# Sprite_CC1310_Development.net
KiCad netlist of a schematic drawn in EAGLE
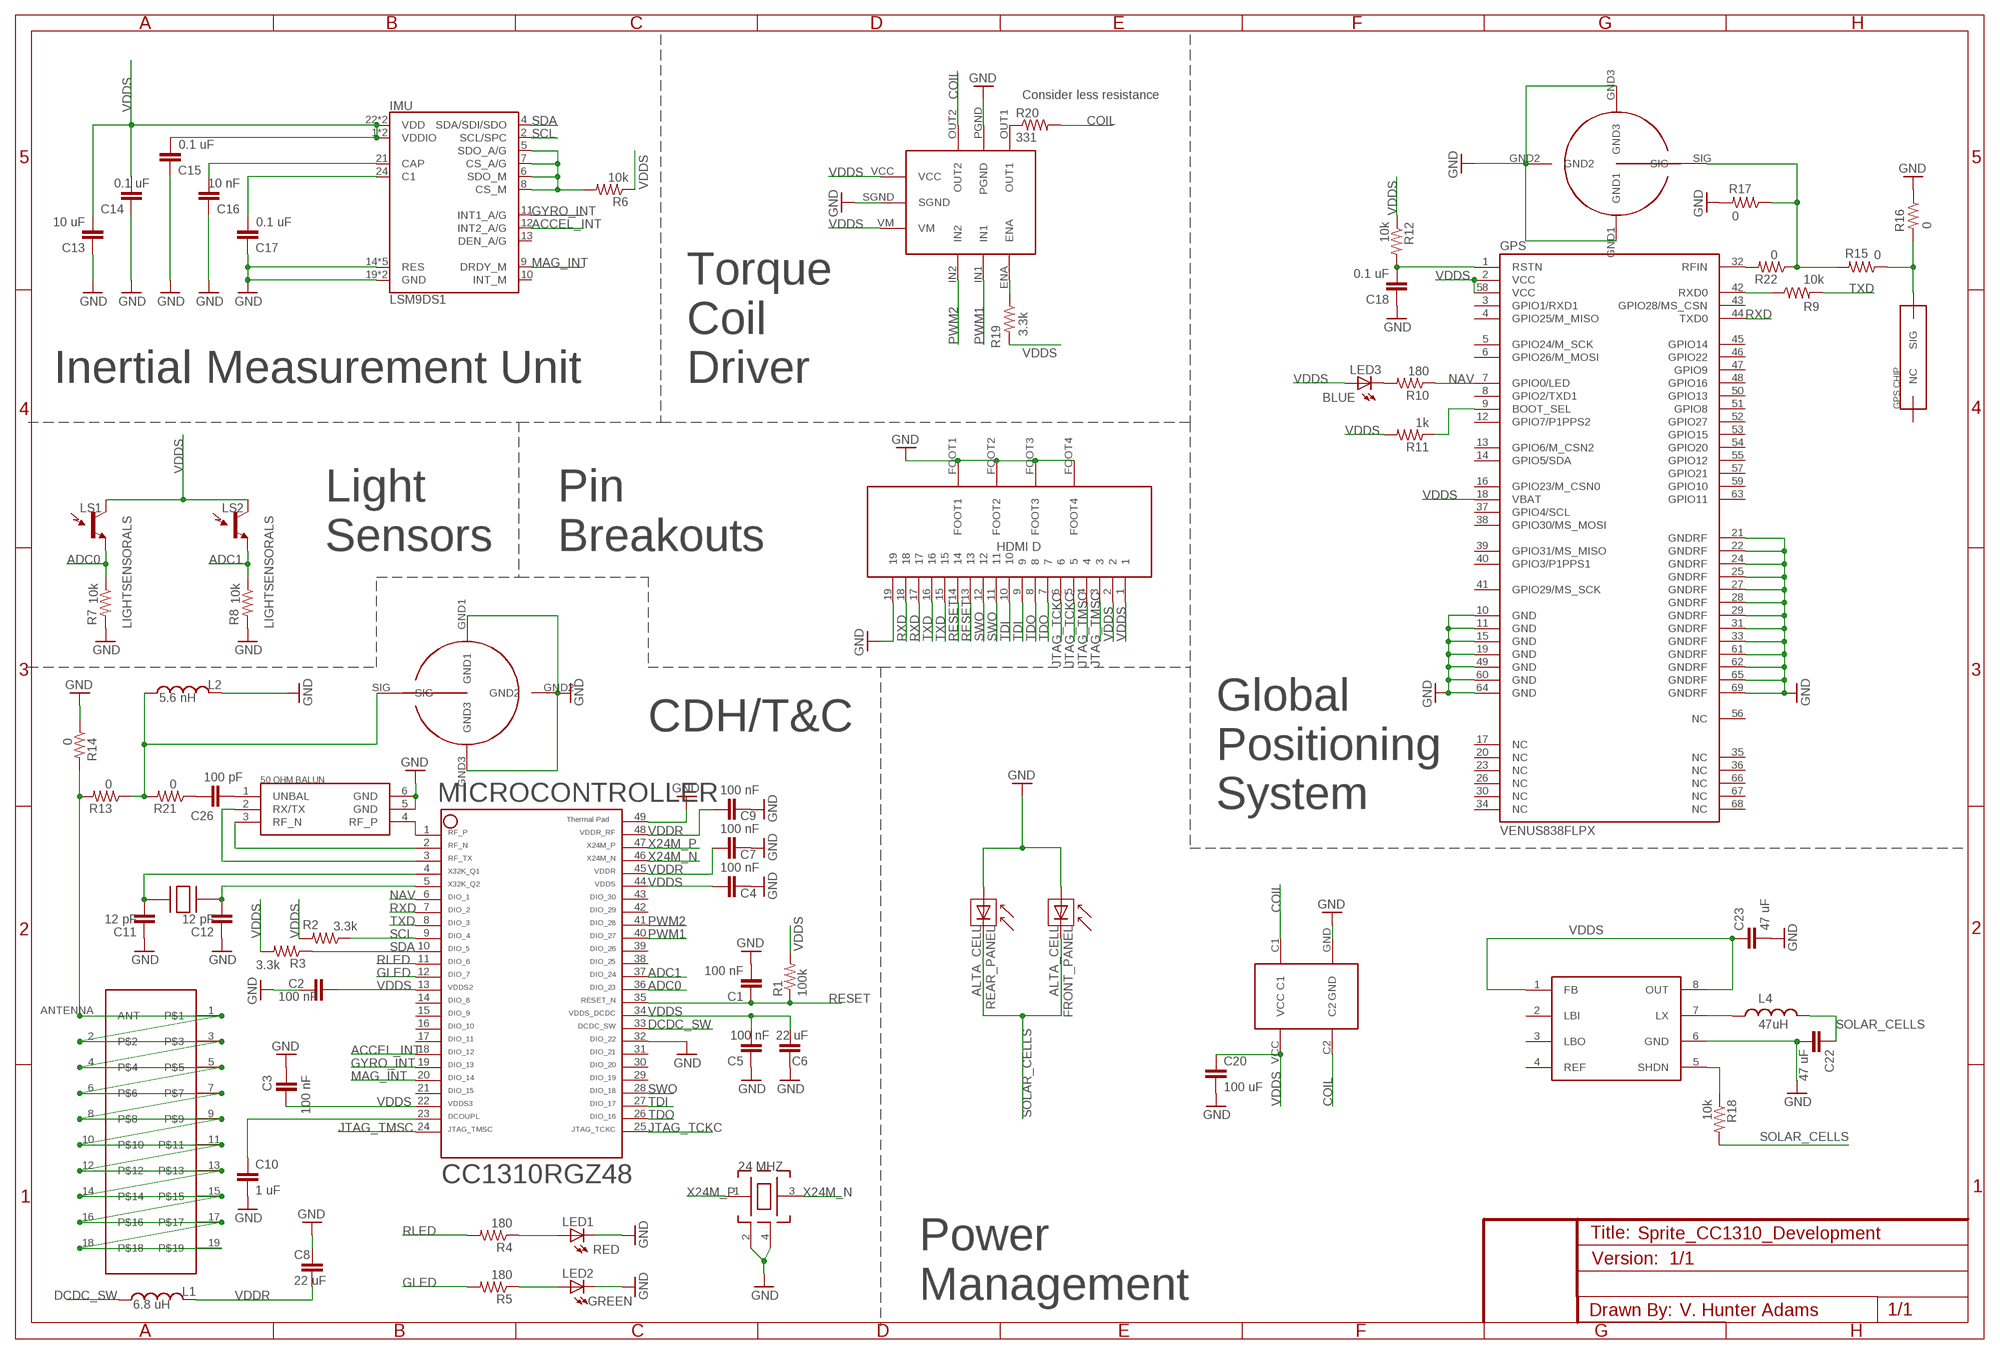
[diagram p0: schematic, sheet 1]

(export (version "E")
  (design (tool "Eeschema 10.0.6"))
  (components
    (comp (ref "32.768")
      (value "FC-135")
      (footprint "eagle-import:FC-135")
      (libsource (lib "eagle-import") (part "FC-135"))
    )
    (comp (ref "BALUN")
      (value "JOHANSON_BALUN")
      (footprint "eagle-import:JOHANSON_BALUN")
      (libsource (lib "eagle-import") (part "JOHANSON_BALUN"))
    )
    (comp (ref "C1")
      (value "100 nF")
      (footprint "eagle-import:0402-CAP")
      (libsource (lib "eagle-import") (part "CAP0402-CAP"))
    )
    (comp (ref "C2")
      (value "100 nF")
      (footprint "eagle-import:0402-CAP")
      (libsource (lib "eagle-import") (part "CAP0402-CAP"))
    )
    (comp (ref "C3")
      (value "100 nF")
      (footprint "eagle-import:0402-CAP")
      (libsource (lib "eagle-import") (part "CAP0402-CAP"))
    )
    (comp (ref "C4")
      (value "100 nF")
      (footprint "eagle-import:0402-CAP")
      (libsource (lib "eagle-import") (part "CAP0402-CAP"))
    )
    (comp (ref "C5")
      (value "100 nF")
      (footprint "eagle-import:0402-CAP")
      (libsource (lib "eagle-import") (part "CAP0402-CAP"))
    )
    (comp (ref "C6")
      (value "22 uF")
      (footprint "eagle-import:0402-CAP")
      (libsource (lib "eagle-import") (part "CAP0402-CAP"))
    )
    (comp (ref "C7")
      (value "100 nF")
      (footprint "eagle-import:0402-CAP")
      (libsource (lib "eagle-import") (part "CAP0402-CAP"))
    )
    (comp (ref "C8")
      (value "22 uF")
      (footprint "eagle-import:0402-CAP")
      (libsource (lib "eagle-import") (part "CAP0402-CAP"))
    )
    (comp (ref "C9")
      (value "100 nF")
      (footprint "eagle-import:0402-CAP")
      (libsource (lib "eagle-import") (part "CAP0402-CAP"))
    )
    (comp (ref "C10")
      (value "1 uF")
      (footprint "eagle-import:0402-CAP")
      (libsource (lib "eagle-import") (part "CAP0402-CAP"))
    )
    (comp (ref "C11")
      (value "12 pF")
      (footprint "eagle-import:0402-CAP")
      (libsource (lib "eagle-import") (part "CAP0402-CAP"))
    )
    (comp (ref "C12")
      (value "12 pF")
      (footprint "eagle-import:0402-CAP")
      (libsource (lib "eagle-import") (part "CAP0402-CAP"))
    )
    (comp (ref "C13")
      (value "10 uF")
      (footprint "eagle-import:0402-CAP")
      (libsource (lib "eagle-import") (part "CAP0402-CAP"))
    )
    (comp (ref "C14")
      (value "0.1 uF")
      (footprint "eagle-import:0402-CAP")
      (libsource (lib "eagle-import") (part "CAP0402-CAP"))
    )
    (comp (ref "C15")
      (value "0.1 uF")
      (footprint "eagle-import:0402-CAP")
      (libsource (lib "eagle-import") (part "CAP0402-CAP"))
    )
    (comp (ref "C16")
      (value "10 nF")
      (footprint "eagle-import:0402-CAP")
      (libsource (lib "eagle-import") (part "CAP0402-CAP"))
    )
    (comp (ref "C17")
      (value "0.1 uF")
      (footprint "eagle-import:0402-CAP")
      (libsource (lib "eagle-import") (part "CAP0402-CAP"))
    )
    (comp (ref "C18")
      (value "0.1 uF")
      (footprint "eagle-import:0402-CAP")
      (libsource (lib "eagle-import") (part "CAP0402-CAP"))
    )
    (comp (ref "C20")
      (value "100 uF")
      (footprint "eagle-import:0805")
      (libsource (lib "eagle-import") (part "CAP0805"))
    )
    (comp (ref "C22")
      (value "47 uF")
      (footprint "eagle-import:0805")
      (libsource (lib "eagle-import") (part "CAP0805"))
    )
    (comp (ref "C23")
      (value "47 uF")
      (footprint "eagle-import:0805")
      (libsource (lib "eagle-import") (part "CAP0805"))
    )
    (comp (ref "C26")
      (value "100 pF")
      (footprint "eagle-import:0402-CAP")
      (libsource (lib "eagle-import") (part "CAP0402-CAP"))
    )
    (comp (ref "FRONT_PANEL")
      (value "ALTA_CELL")
      (footprint "eagle-import:ALTA_CELL")
      (libsource (lib "eagle-import") (part "ALTA_CELL"))
    )
    (comp (ref "GPS")
      (value "VENUS838FLPX")
      (footprint "eagle-import:VENUS838FLPX")
      (libsource (lib "eagle-import") (part "VENUS838FLPX"))
    )
    (comp (ref "IMU")
      (value "LSM9DS1")
      (footprint "eagle-import:LGA24-8X4")
      (libsource (lib "eagle-import") (part "LSM9DS1"))
    )
    (comp (ref "L1")
      (value "6.8 uH")
      (footprint "eagle-import:0603")
      (libsource (lib "eagle-import") (part "INDUCTOR0603"))
    )
    (comp (ref "L2")
      (value "5.6 nH")
      (footprint "eagle-import:0603")
      (libsource (lib "eagle-import") (part "INDUCTOR0603"))
    )
    (comp (ref "L4")
      (value "47uH")
      (footprint "eagle-import:0603")
      (libsource (lib "eagle-import") (part "INDUCTOR0603"))
    )
    (comp (ref "LED1")
      (value "RED")
      (footprint "eagle-import:LED-0603")
      (libsource (lib "eagle-import") (part "LED0603"))
    )
    (comp (ref "LED2")
      (value "GREEN")
      (footprint "eagle-import:LED-0603")
      (libsource (lib "eagle-import") (part "LED0603"))
    )
    (comp (ref "LED3")
      (value "BLUE")
      (footprint "eagle-import:LED-0603")
      (libsource (lib "eagle-import") (part "LED0603"))
    )
    (comp (ref "LS1")
      (value "LIGHTSENSORALS")
      (footprint "eagle-import:ALS-PT19")
      (libsource (lib "eagle-import") (part "LIGHTSENSORALS"))
    )
    (comp (ref "LS2")
      (value "LIGHTSENSORALS")
      (footprint "eagle-import:ALS-PT19")
      (libsource (lib "eagle-import") (part "LIGHTSENSORALS"))
    )
    (comp (ref "MICROCONTROLLER")
      (value "CC1310")
      (footprint "eagle-import:CC1310")
      (libsource (lib "eagle-import") (part "CC1310"))
    )
    (comp (ref "R1")
      (value "100k")
      (footprint "eagle-import:0402-RES")
      (libsource (lib "eagle-import") (part "RESISTOR0402-RES"))
    )
    (comp (ref "R2")
      (value "3.3k")
      (footprint "eagle-import:0402-RES")
      (libsource (lib "eagle-import") (part "RESISTOR0402-RES"))
    )
    (comp (ref "R3")
      (value "3.3k")
      (footprint "eagle-import:0402-RES")
      (libsource (lib "eagle-import") (part "RESISTOR0402-RES"))
    )
    (comp (ref "R4")
      (value "180")
      (footprint "eagle-import:0402-RES")
      (libsource (lib "eagle-import") (part "RESISTOR0402-RES"))
    )
    (comp (ref "R5")
      (value "180")
      (footprint "eagle-import:0402-RES")
      (libsource (lib "eagle-import") (part "RESISTOR0402-RES"))
    )
    (comp (ref "R6")
      (value "10k")
      (footprint "eagle-import:0402-RES")
      (libsource (lib "eagle-import") (part "RESISTOR0402-RES"))
    )
    (comp (ref "R7")
      (value "10k")
      (footprint "eagle-import:0402-RES")
      (libsource (lib "eagle-import") (part "RESISTOR0402-RES"))
    )
    (comp (ref "R8")
      (value "10k")
      (footprint "eagle-import:0402-RES")
      (libsource (lib "eagle-import") (part "RESISTOR0402-RES"))
    )
    (comp (ref "R9")
      (value "10k")
      (footprint "eagle-import:0402-RES")
      (libsource (lib "eagle-import") (part "RESISTOR0402-RES"))
    )
    (comp (ref "R10")
      (value "180")
      (footprint "eagle-import:0402-RES")
      (libsource (lib "eagle-import") (part "RESISTOR0402-RES"))
    )
    (comp (ref "R11")
      (value "1k")
      (footprint "eagle-import:0402-RES")
      (libsource (lib "eagle-import") (part "RESISTOR0402-RES"))
    )
    (comp (ref "R12")
      (value "10k")
      (footprint "eagle-import:0402-RES")
      (libsource (lib "eagle-import") (part "RESISTOR0402-RES"))
    )
    (comp (ref "R13")
      (value "0")
      (footprint "eagle-import:0603-RES")
      (libsource (lib "eagle-import") (part "RESISTOR0603-RES"))
    )
    (comp (ref "R14")
      (value "0")
      (footprint "eagle-import:0603-RES")
      (libsource (lib "eagle-import") (part "RESISTOR0603-RES"))
    )
    (comp (ref "R15")
      (value "0")
      (footprint "eagle-import:0603-RES")
      (libsource (lib "eagle-import") (part "RESISTOR0603-RES"))
    )
    (comp (ref "R16")
      (value "0")
      (footprint "eagle-import:0603-RES")
      (libsource (lib "eagle-import") (part "RESISTOR0603-RES"))
    )
    (comp (ref "R17")
      (value "0")
      (footprint "eagle-import:0603-RES")
      (libsource (lib "eagle-import") (part "RESISTOR0603-RES"))
    )
    (comp (ref "R18")
      (value "10k")
      (footprint "eagle-import:0402-RES")
      (libsource (lib "eagle-import") (part "RESISTOR0402-RES"))
    )
    (comp (ref "R19")
      (value "3.3k")
      (footprint "eagle-import:0402-RES")
      (libsource (lib "eagle-import") (part "RESISTOR0402-RES"))
    )
    (comp (ref "R20")
      (value "331")
      (footprint "eagle-import:0402-RES")
      (libsource (lib "eagle-import") (part "RESISTOR0402-RES"))
    )
    (comp (ref "R21")
      (value "0")
      (footprint "eagle-import:0603-RES")
      (libsource (lib "eagle-import") (part "RESISTOR0603-RES"))
    )
    (comp (ref "R22")
      (value "0")
      (footprint "eagle-import:0603-RES")
      (libsource (lib "eagle-import") (part "RESISTOR0603-RES"))
    )
    (comp (ref "REAR_PANEL")
      (value "ALTA_CELL")
      (footprint "eagle-import:ALTA_CELL")
      (libsource (lib "eagle-import") (part "ALTA_CELL"))
    )
    (comp (ref "TSX3225")
      (value "TSX-3225")
      (footprint "eagle-import:TSX-3225")
      (libsource (lib "eagle-import") (part "TSX-3225"))
    )
    (comp (ref "U$1")
      (value "HDMID")
      (footprint "eagle-import:HDMID")
      (libsource (lib "eagle-import") (part "HDMID"))
    )
    (comp (ref "U$2")
      (value "LV8417CS")
      (footprint "eagle-import:LV8417CS")
      (libsource (lib "eagle-import") (part "LV8417CS"))
    )
    (comp (ref "U$3")
      (value "MM5329-2700")
      (footprint "eagle-import:MM5829-2700")
      (libsource (lib "eagle-import") (part "MM5329-2700"))
    )
    (comp (ref "U$4")
      (value "PANASONIC_RECTIFIER")
      (footprint "eagle-import:PANASONIC_RECTIFIER")
      (libsource (lib "eagle-import") (part "PANASONIC_RECTIFIER"))
    )
    (comp (ref "U$5")
      (value "JOHANSON_GPS_CHIP")
      (footprint "eagle-import:JOHANSON_GPS_CHIP")
      (libsource (lib "eagle-import") (part "JOHANSON_GPS_CHIP"))
    )
    (comp (ref "U$6")
      (value "PCB_ANTENNA")
      (footprint "eagle-import:PCB_ANTENNA")
      (libsource (lib "eagle-import") (part "PCB_ANTENNA"))
    )
    (comp (ref "U$7")
      (value "MM5329-2700")
      (footprint "eagle-import:MM5829-2700")
      (libsource (lib "eagle-import") (part "MM5329-2700"))
    )
    (comp (ref "U$8")
      (value "L6920")
      (footprint "eagle-import:L6920")
      (libsource (lib "eagle-import") (part "L6920"))
    )
  )
  (nets
    (net (code "1") (name "/ACCEL_INT") (class "Default")
      (node (ref "IMU") (pin "12") (pinfunction "INT2_A/G_12") (pintype "bidirectional"))
      (node (ref "MICROCONTROLLER") (pin "18") (pinfunction "18_18") (pintype "bidirectional"))
    )
    (net (code "2") (name "/ADC0") (class "Default")
      (node (ref "LS1") (pin "E") (pinfunction "E1_E") (pintype "passive"))
      (node (ref "MICROCONTROLLER") (pin "36") (pinfunction "36_36") (pintype "bidirectional"))
      (node (ref "R7") (pin "1") (pinfunction "1_1") (pintype "passive"))
    )
    (net (code "3") (name "/ADC1") (class "Default")
      (node (ref "LS2") (pin "E") (pinfunction "E1_E") (pintype "passive"))
      (node (ref "MICROCONTROLLER") (pin "37") (pinfunction "37_37") (pintype "bidirectional"))
      (node (ref "R8") (pin "1") (pinfunction "1_1") (pintype "passive"))
    )
    (net (code "4") (name "/COIL") (class "Default")
      (node (ref "R20") (pin "2") (pinfunction "2_2") (pintype "passive"))
      (node (ref "U$2") (pin "OUT2") (pinfunction "OUT2_OUT2") (pintype "bidirectional"))
      (node (ref "U$4") (pin "C1") (pinfunction "C1_C1") (pintype "bidirectional"))
      (node (ref "U$4") (pin "C2") (pinfunction "C2_C2") (pintype "bidirectional"))
    )
    (net (code "5") (name "/DCDC_SW") (class "Default")
      (node (ref "L1") (pin "1") (pinfunction "1_1") (pintype "passive"))
      (node (ref "MICROCONTROLLER") (pin "33") (pinfunction "33_33") (pintype "power_in"))
    )
    (net (code "6") (name "/GLED") (class "Default")
      (node (ref "MICROCONTROLLER") (pin "12") (pinfunction "12_12") (pintype "bidirectional"))
      (node (ref "R5") (pin "2") (pinfunction "2_2") (pintype "passive"))
    )
    (net (code "7") (name "/GYRO_INT") (class "Default")
      (node (ref "IMU") (pin "11") (pinfunction "INT1_A/G_11") (pintype "bidirectional"))
      (node (ref "MICROCONTROLLER") (pin "19") (pinfunction "19_19") (pintype "bidirectional"))
    )
    (net (code "8") (name "/JTAG_TCKC") (class "Default")
      (node (ref "MICROCONTROLLER") (pin "25") (pinfunction "25_25") (pintype "input"))
      (node (ref "U$1") (pin "5") (pinfunction "5_5") (pintype "bidirectional"))
      (node (ref "U$1") (pin "6") (pinfunction "6_6") (pintype "bidirectional"))
    )
    (net (code "9") (name "/JTAG_TMSC") (class "Default")
      (node (ref "MICROCONTROLLER") (pin "24") (pinfunction "24_24") (pintype "bidirectional"))
      (node (ref "U$1") (pin "3") (pinfunction "3_3") (pintype "bidirectional"))
      (node (ref "U$1") (pin "4") (pinfunction "4_4") (pintype "bidirectional"))
    )
    (net (code "10") (name "/MAG_INT") (class "Default")
      (node (ref "IMU") (pin "9") (pinfunction "DRDY_M_9") (pintype "bidirectional"))
      (node (ref "MICROCONTROLLER") (pin "20") (pinfunction "20_20") (pintype "bidirectional"))
    )
    (net (code "11") (name "/NAV") (class "Default")
      (node (ref "GPS") (pin "7") (pinfunction "GPIO0/LED_7") (pintype "bidirectional"))
      (node (ref "MICROCONTROLLER") (pin "6") (pinfunction "6_6") (pintype "bidirectional"))
      (node (ref "R10") (pin "1") (pinfunction "1_1") (pintype "passive"))
    )
    (net (code "12") (name "/PWM1") (class "Default")
      (node (ref "MICROCONTROLLER") (pin "40") (pinfunction "40_40") (pintype "bidirectional"))
      (node (ref "U$2") (pin "IN1") (pinfunction "IN1_IN1") (pintype "bidirectional"))
    )
    (net (code "13") (name "/PWM2") (class "Default")
      (node (ref "MICROCONTROLLER") (pin "41") (pinfunction "41_41") (pintype "bidirectional"))
      (node (ref "U$2") (pin "IN2") (pinfunction "IN2_IN2") (pintype "bidirectional"))
    )
    (net (code "14") (name "/RESET") (class "Default")
      (node (ref "C1") (pin "1") (pinfunction "1_1") (pintype "passive"))
      (node (ref "MICROCONTROLLER") (pin "35") (pinfunction "35_35") (pintype "input"))
      (node (ref "R1") (pin "1") (pinfunction "1_1") (pintype "passive"))
      (node (ref "U$1") (pin "13") (pinfunction "13_13") (pintype "bidirectional"))
      (node (ref "U$1") (pin "14") (pinfunction "14_14") (pintype "bidirectional"))
    )
    (net (code "15") (name "/RLED") (class "Default")
      (node (ref "MICROCONTROLLER") (pin "11") (pinfunction "11_11") (pintype "bidirectional"))
      (node (ref "R4") (pin "2") (pinfunction "2_2") (pintype "passive"))
    )
    (net (code "16") (name "/RXD") (class "Default")
      (node (ref "GPS") (pin "44") (pinfunction "TXD0_44") (pintype "bidirectional"))
      (node (ref "MICROCONTROLLER") (pin "7") (pinfunction "7_7") (pintype "bidirectional"))
      (node (ref "U$1") (pin "17") (pinfunction "17_17") (pintype "bidirectional"))
      (node (ref "U$1") (pin "18") (pinfunction "18_18") (pintype "bidirectional"))
    )
    (net (code "17") (name "/SCL") (class "Default")
      (node (ref "IMU") (pin "2") (pinfunction "SCL/SPC_2") (pintype "bidirectional"))
      (node (ref "MICROCONTROLLER") (pin "9") (pinfunction "9_9") (pintype "bidirectional"))
      (node (ref "R2") (pin "1") (pinfunction "1_1") (pintype "passive"))
    )
    (net (code "18") (name "/SDA") (class "Default")
      (node (ref "IMU") (pin "4") (pinfunction "SDA/SDI/SDO_4") (pintype "bidirectional"))
      (node (ref "MICROCONTROLLER") (pin "10") (pinfunction "10_10") (pintype "bidirectional"))
      (node (ref "R3") (pin "1") (pinfunction "1_1") (pintype "passive"))
    )
    (net (code "19") (name "/SOLAR_CELLS") (class "Default")
      (node (ref "C22") (pin "1") (pinfunction "1_1") (pintype "passive"))
      (node (ref "FRONT_PANEL") (pin "+") (pinfunction "+_+") (pintype "passive"))
      (node (ref "L4") (pin "2") (pinfunction "2_2") (pintype "passive"))
      (node (ref "R18") (pin "2") (pinfunction "2_2") (pintype "passive"))
      (node (ref "REAR_PANEL") (pin "+") (pinfunction "+_+") (pintype "passive"))
    )
    (net (code "20") (name "/SWO") (class "Default")
      (node (ref "MICROCONTROLLER") (pin "28") (pinfunction "28_28") (pintype "bidirectional"))
      (node (ref "U$1") (pin "11") (pinfunction "11_11") (pintype "bidirectional"))
      (node (ref "U$1") (pin "12") (pinfunction "12_12") (pintype "bidirectional"))
    )
    (net (code "21") (name "/TDI") (class "Default")
      (node (ref "MICROCONTROLLER") (pin "27") (pinfunction "27_27") (pintype "bidirectional"))
      (node (ref "U$1") (pin "10") (pinfunction "10_10") (pintype "bidirectional"))
      (node (ref "U$1") (pin "9") (pinfunction "9_9") (pintype "bidirectional"))
    )
    (net (code "22") (name "/TDO") (class "Default")
      (node (ref "MICROCONTROLLER") (pin "26") (pinfunction "26_26") (pintype "bidirectional"))
      (node (ref "U$1") (pin "7") (pinfunction "7_7") (pintype "bidirectional"))
      (node (ref "U$1") (pin "8") (pinfunction "8_8") (pintype "bidirectional"))
    )
    (net (code "23") (name "/TXD") (class "Default")
      (node (ref "MICROCONTROLLER") (pin "8") (pinfunction "8_8") (pintype "bidirectional"))
      (node (ref "R9") (pin "2") (pinfunction "2_2") (pintype "passive"))
      (node (ref "U$1") (pin "15") (pinfunction "15_15") (pintype "bidirectional"))
      (node (ref "U$1") (pin "16") (pinfunction "16_16") (pintype "bidirectional"))
    )
    (net (code "24") (name "/VDDR") (class "Default")
      (node (ref "C7") (pin "1") (pinfunction "1_1") (pintype "passive"))
      (node (ref "C8") (pin "1") (pinfunction "1_1") (pintype "passive"))
      (node (ref "C9") (pin "1") (pinfunction "1_1") (pintype "passive"))
      (node (ref "L1") (pin "2") (pinfunction "2_2") (pintype "passive"))
      (node (ref "MICROCONTROLLER") (pin "45") (pinfunction "45_45") (pintype "power_in"))
      (node (ref "MICROCONTROLLER") (pin "48") (pinfunction "48_48") (pintype "power_in"))
    )
    (net (code "25") (name "/VDDS") (class "Default")
      (node (ref "C13") (pin "1") (pinfunction "1_1") (pintype "passive"))
      (node (ref "C14") (pin "1") (pinfunction "1_1") (pintype "passive"))
      (node (ref "C15") (pin "1") (pinfunction "1_1") (pintype "passive"))
      (node (ref "C2") (pin "1") (pinfunction "1_1") (pintype "passive"))
      (node (ref "C20") (pin "1") (pinfunction "1_1") (pintype "passive"))
      (node (ref "C23") (pin "1") (pinfunction "1_1") (pintype "passive"))
      (node (ref "C3") (pin "1") (pinfunction "1_1") (pintype "passive"))
      (node (ref "C4") (pin "1") (pinfunction "1_1") (pintype "passive"))
      (node (ref "C5") (pin "1") (pinfunction "1_1") (pintype "passive"))
      (node (ref "C6") (pin "1") (pinfunction "1_1") (pintype "passive"))
      (node (ref "GPS") (pin "18") (pinfunction "VBAT_18") (pintype "bidirectional"))
      (node (ref "GPS") (pin "2") (pinfunction "VCC_2") (pintype "bidirectional"))
      (node (ref "GPS") (pin "58") (pinfunction "VCC_58") (pintype "bidirectional"))
      (node (ref "IMU") (pin "1") (pinfunction "VDDIO_1") (pintype "bidirectional"))
      (node (ref "IMU") (pin "22") (pinfunction "VDD_22") (pintype "bidirectional"))
      (node (ref "IMU") (pin "23") (pinfunction "VDD_23") (pintype "bidirectional"))
      (node (ref "IMU") (pin "3") (pinfunction "VDDIO_3") (pintype "bidirectional"))
      (node (ref "LED3") (pin "A") (pinfunction "A_A") (pintype "passive"))
      (node (ref "LS1") (pin "C") (pinfunction "C1_C") (pintype "passive"))
      (node (ref "LS2") (pin "C") (pinfunction "C1_C") (pintype "passive"))
      (node (ref "MICROCONTROLLER") (pin "13") (pinfunction "13_13") (pintype "bidirectional"))
      (node (ref "MICROCONTROLLER") (pin "22") (pinfunction "22_22") (pintype "power_in"))
      (node (ref "MICROCONTROLLER") (pin "34") (pinfunction "34_34") (pintype "power_in"))
      (node (ref "MICROCONTROLLER") (pin "44") (pinfunction "44_44") (pintype "power_in"))
      (node (ref "R1") (pin "2") (pinfunction "2_2") (pintype "passive"))
      (node (ref "R11") (pin "2") (pinfunction "2_2") (pintype "passive"))
      (node (ref "R12") (pin "1") (pinfunction "1_1") (pintype "passive"))
      (node (ref "R19") (pin "2") (pinfunction "2_2") (pintype "passive"))
      (node (ref "R2") (pin "2") (pinfunction "2_2") (pintype "passive"))
      (node (ref "R3") (pin "2") (pinfunction "2_2") (pintype "passive"))
      (node (ref "R6") (pin "1") (pinfunction "1_1") (pintype "passive"))
      (node (ref "U$1") (pin "1") (pinfunction "1_1") (pintype "bidirectional"))
      (node (ref "U$1") (pin "2") (pinfunction "2_2") (pintype "bidirectional"))
      (node (ref "U$2") (pin "VCC") (pinfunction "VCC_VCC") (pintype "bidirectional"))
      (node (ref "U$2") (pin "VM") (pinfunction "VM_VM") (pintype "bidirectional"))
      (node (ref "U$4") (pin "VCC") (pinfunction "VCC_VCC") (pintype "bidirectional"))
      (node (ref "U$8") (pin "1") (pinfunction "FB_1") (pintype "bidirectional"))
      (node (ref "U$8") (pin "8") (pinfunction "OUT_8") (pintype "bidirectional"))
    )
    (net (code "26") (name "/X24M_N") (class "Default")
      (node (ref "MICROCONTROLLER") (pin "46") (pinfunction "46_46") (pintype "bidirectional"))
      (node (ref "TSX3225") (pin "3") (pinfunction "3_3") (pintype "bidirectional"))
    )
    (net (code "27") (name "/X24M_P") (class "Default")
      (node (ref "MICROCONTROLLER") (pin "47") (pinfunction "47_47") (pintype "input"))
      (node (ref "TSX3225") (pin "1") (pinfunction "1_1") (pintype "bidirectional"))
    )
    (net (code "28") (name "GND") (class "Default")
      (node (ref "BALUN") (pin "5") (pinfunction "GND_5") (pintype "bidirectional"))
      (node (ref "BALUN") (pin "6") (pinfunction "GND_6") (pintype "bidirectional"))
      (node (ref "C1") (pin "2") (pinfunction "2_2") (pintype "passive"))
      (node (ref "C10") (pin "2") (pinfunction "2_2") (pintype "passive"))
      (node (ref "C11") (pin "2") (pinfunction "2_2") (pintype "passive"))
      (node (ref "C12") (pin "2") (pinfunction "2_2") (pintype "passive"))
      (node (ref "C13") (pin "2") (pinfunction "2_2") (pintype "passive"))
      (node (ref "C14") (pin "2") (pinfunction "2_2") (pintype "passive"))
      (node (ref "C15") (pin "2") (pinfunction "2_2") (pintype "passive"))
      (node (ref "C16") (pin "2") (pinfunction "2_2") (pintype "passive"))
      (node (ref "C17") (pin "2") (pinfunction "2_2") (pintype "passive"))
      (node (ref "C18") (pin "2") (pinfunction "2_2") (pintype "passive"))
      (node (ref "C2") (pin "2") (pinfunction "2_2") (pintype "passive"))
      (node (ref "C20") (pin "2") (pinfunction "2_2") (pintype "passive"))
      (node (ref "C22") (pin "2") (pinfunction "2_2") (pintype "passive"))
      (node (ref "C23") (pin "2") (pinfunction "2_2") (pintype "passive"))
      (node (ref "C3") (pin "2") (pinfunction "2_2") (pintype "passive"))
      (node (ref "C4") (pin "2") (pinfunction "2_2") (pintype "passive"))
      (node (ref "C5") (pin "2") (pinfunction "2_2") (pintype "passive"))
      (node (ref "C6") (pin "2") (pinfunction "2_2") (pintype "passive"))
      (node (ref "C7") (pin "2") (pinfunction "2_2") (pintype "passive"))
      (node (ref "C8") (pin "2") (pinfunction "2_2") (pintype "passive"))
      (node (ref "C9") (pin "2") (pinfunction "2_2") (pintype "passive"))
      (node (ref "FRONT_PANEL") (pin "-") (pinfunction "-_-") (pintype "passive"))
      (node (ref "GPS") (pin "10") (pinfunction "GND_10") (pintype "bidirectional"))
      (node (ref "GPS") (pin "11") (pinfunction "GND_11") (pintype "bidirectional"))
      (node (ref "GPS") (pin "15") (pinfunction "GND_15") (pintype "bidirectional"))
      (node (ref "GPS") (pin "19") (pinfunction "GND_19") (pintype "bidirectional"))
      (node (ref "GPS") (pin "21") (pinfunction "GNDRF_21") (pintype "bidirectional"))
      (node (ref "GPS") (pin "22") (pinfunction "GNDRF_22") (pintype "bidirectional"))
      (node (ref "GPS") (pin "24") (pinfunction "GNDRF_24") (pintype "bidirectional"))
      (node (ref "GPS") (pin "25") (pinfunction "GNDRF_25") (pintype "bidirectional"))
      (node (ref "GPS") (pin "27") (pinfunction "GNDRF_27") (pintype "bidirectional"))
      (node (ref "GPS") (pin "28") (pinfunction "GNDRF_28") (pintype "bidirectional"))
      (node (ref "GPS") (pin "29") (pinfunction "GNDRF_29") (pintype "bidirectional"))
      (node (ref "GPS") (pin "31") (pinfunction "GNDRF_31") (pintype "bidirectional"))
      (node (ref "GPS") (pin "33") (pinfunction "GNDRF_33") (pintype "bidirectional"))
      (node (ref "GPS") (pin "49") (pinfunction "GND_49") (pintype "bidirectional"))
      (node (ref "GPS") (pin "60") (pinfunction "GND_60") (pintype "bidirectional"))
      (node (ref "GPS") (pin "61") (pinfunction "GNDRF_61") (pintype "bidirectional"))
      (node (ref "GPS") (pin "62") (pinfunction "GNDRF_62") (pintype "bidirectional"))
      (node (ref "GPS") (pin "64") (pinfunction "GND_64") (pintype "bidirectional"))
      (node (ref "GPS") (pin "65") (pinfunction "GNDRF_65") (pintype "bidirectional"))
      (node (ref "GPS") (pin "69") (pinfunction "GNDRF_69") (pintype "bidirectional"))
      (node (ref "IMU") (pin "14") (pinfunction "RES_14") (pintype "bidirectional"))
      (node (ref "IMU") (pin "15") (pinfunction "RES_15") (pintype "bidirectional"))
      (node (ref "IMU") (pin "16") (pinfunction "RES_16") (pintype "bidirectional"))
      (node (ref "IMU") (pin "17") (pinfunction "RES_17") (pintype "bidirectional"))
      (node (ref "IMU") (pin "18") (pinfunction "RES_18") (pintype "bidirectional"))
      (node (ref "IMU") (pin "19") (pinfunction "GND_19") (pintype "bidirectional"))
      (node (ref "IMU") (pin "20") (pinfunction "GND_20") (pintype "bidirectional"))
      (node (ref "L2") (pin "2") (pinfunction "2_2") (pintype "passive"))
      (node (ref "LED1") (pin "C") (pinfunction "C_C") (pintype "passive"))
      (node (ref "LED2") (pin "C") (pinfunction "C_C") (pintype "passive"))
      (node (ref "MICROCONTROLLER") (pin "32") (pinfunction "32_32") (pintype "bidirectional"))
      (node (ref "MICROCONTROLLER") (pin "49") (pinfunction "49_49") (pintype "input"))
      (node (ref "R14") (pin "1") (pinfunction "1_1") (pintype "passive"))
      (node (ref "R16") (pin "1") (pinfunction "1_1") (pintype "passive"))
      (node (ref "R17") (pin "2") (pinfunction "2_2") (pintype "passive"))
      (node (ref "R7") (pin "2") (pinfunction "2_2") (pintype "passive"))
      (node (ref "R8") (pin "2") (pinfunction "2_2") (pintype "passive"))
      (node (ref "REAR_PANEL") (pin "-") (pinfunction "-_-") (pintype "passive"))
      (node (ref "TSX3225") (pin "2") (pinfunction "2_2") (pintype "bidirectional"))
      (node (ref "TSX3225") (pin "4") (pinfunction "4_4") (pintype "bidirectional"))
      (node (ref "U$1") (pin "19") (pinfunction "19_19") (pintype "bidirectional"))
      (node (ref "U$1") (pin "FOOT1") (pinfunction "FOOT1_FOOT1") (pintype "bidirectional"))
      (node (ref "U$1") (pin "FOOT2") (pinfunction "FOOT2_FOOT2") (pintype "bidirectional"))
      (node (ref "U$1") (pin "FOOT3") (pinfunction "FOOT3_FOOT3") (pintype "bidirectional"))
      (node (ref "U$1") (pin "FOOT4") (pinfunction "FOOT4_FOOT4") (pintype "bidirectional"))
      (node (ref "U$2") (pin "PGND") (pinfunction "PGND_PGND") (pintype "bidirectional"))
      (node (ref "U$2") (pin "SGND") (pinfunction "SGND_SGND") (pintype "bidirectional"))
      (node (ref "U$3") (pin "GND1") (pinfunction "GND1_GND1") (pintype "bidirectional"))
      (node (ref "U$3") (pin "GND2") (pinfunction "GND2_GND2") (pintype "bidirectional"))
      (node (ref "U$3") (pin "GND3") (pinfunction "GND3_GND3") (pintype "bidirectional"))
      (node (ref "U$4") (pin "GND") (pinfunction "GND_GND") (pintype "bidirectional"))
      (node (ref "U$7") (pin "GND1") (pinfunction "GND1_GND1") (pintype "bidirectional"))
      (node (ref "U$7") (pin "GND2") (pinfunction "GND2_GND2") (pintype "bidirectional"))
      (node (ref "U$7") (pin "GND3") (pinfunction "GND3_GND3") (pintype "bidirectional"))
      (node (ref "U$8") (pin "6") (pinfunction "GND_6") (pintype "bidirectional"))
    )
    (net (code "29") (name "Net-(32.768-PadP1)") (class "Default")
      (node (ref "32.768") (pin "P1") (pinfunction "P1_P1") (pintype "bidirectional"))
      (node (ref "C12") (pin "1") (pinfunction "1_1") (pintype "passive"))
      (node (ref "MICROCONTROLLER") (pin "5") (pinfunction "5_5") (pintype "bidirectional"))
    )
    (net (code "30") (name "Net-(32.768-PadP2)") (class "Default")
      (node (ref "32.768") (pin "P2") (pinfunction "P2_P2") (pintype "bidirectional"))
      (node (ref "C11") (pin "1") (pinfunction "1_1") (pintype "passive"))
      (node (ref "MICROCONTROLLER") (pin "4") (pinfunction "4_4") (pintype "bidirectional"))
    )
    (net (code "31") (name "Net-(BALUN-RF_N)") (class "Default")
      (node (ref "BALUN") (pin "3") (pinfunction "RF_N_3") (pintype "bidirectional"))
      (node (ref "MICROCONTROLLER") (pin "2") (pinfunction "2_2") (pintype "bidirectional"))
    )
    (net (code "32") (name "Net-(BALUN-RF_P)") (class "Default")
      (node (ref "BALUN") (pin "4") (pinfunction "RF_P_4") (pintype "bidirectional"))
      (node (ref "MICROCONTROLLER") (pin "1") (pinfunction "1_1") (pintype "bidirectional"))
    )
    (net (code "33") (name "Net-(BALUN-RX{slash}TX)") (class "Default")
      (node (ref "BALUN") (pin "2") (pinfunction "RX/TX_2") (pintype "bidirectional"))
      (node (ref "MICROCONTROLLER") (pin "3") (pinfunction "3_3") (pintype "bidirectional"))
    )
    (net (code "34") (name "Net-(BALUN-UNBAL)") (class "Default")
      (node (ref "BALUN") (pin "1") (pinfunction "UNBAL_1") (pintype "bidirectional"))
      (node (ref "C26") (pin "2") (pinfunction "2_2") (pintype "passive"))
    )
    (net (code "35") (name "Net-(C10-Pad1)") (class "Default")
      (node (ref "C10") (pin "1") (pinfunction "1_1") (pintype "passive"))
      (node (ref "MICROCONTROLLER") (pin "23") (pinfunction "23_23") (pintype "bidirectional"))
    )
    (net (code "36") (name "Net-(C26-Pad1)") (class "Default")
      (node (ref "C26") (pin "1") (pinfunction "1_1") (pintype "passive"))
      (node (ref "R21") (pin "1") (pinfunction "1_1") (pintype "passive"))
    )
    (net (code "37") (name "Net-(GPS-BOOT_SEL)") (class "Default")
      (node (ref "GPS") (pin "9") (pinfunction "BOOT_SEL_9") (pintype "bidirectional"))
      (node (ref "R11") (pin "1") (pinfunction "1_1") (pintype "passive"))
    )
    (net (code "38") (name "Net-(GPS-RFIN)") (class "Default")
      (node (ref "GPS") (pin "32") (pinfunction "RFIN_32") (pintype "bidirectional"))
      (node (ref "R22") (pin "2") (pinfunction "2_2") (pintype "passive"))
    )
    (net (code "39") (name "Net-(GPS-RSTN)") (class "Default")
      (node (ref "C18") (pin "1") (pinfunction "1_1") (pintype "passive"))
      (node (ref "GPS") (pin "1") (pinfunction "RSTN_1") (pintype "bidirectional"))
      (node (ref "R12") (pin "2") (pinfunction "2_2") (pintype "passive"))
    )
    (net (code "40") (name "Net-(GPS-RXD0)") (class "Default")
      (node (ref "GPS") (pin "42") (pinfunction "RXD0_42") (pintype "bidirectional"))
      (node (ref "R9") (pin "1") (pinfunction "1_1") (pintype "passive"))
    )
    (net (code "41") (name "Net-(IMU-C1)") (class "Default")
      (node (ref "C17") (pin "1") (pinfunction "1_1") (pintype "passive"))
      (node (ref "IMU") (pin "24") (pinfunction "C1_24") (pintype "bidirectional"))
    )
    (net (code "42") (name "Net-(IMU-CAP)") (class "Default")
      (node (ref "C16") (pin "1") (pinfunction "1_1") (pintype "passive"))
      (node (ref "IMU") (pin "21") (pinfunction "CAP_21") (pintype "bidirectional"))
    )
    (net (code "43") (name "Net-(IMU-CS_A{slash}G)") (class "Default")
      (node (ref "IMU") (pin "5") (pinfunction "SDO_A/G_5") (pintype "bidirectional"))
      (node (ref "IMU") (pin "6") (pinfunction "SDO_M_6") (pintype "bidirectional"))
      (node (ref "IMU") (pin "7") (pinfunction "CS_A/G_7") (pintype "bidirectional"))
      (node (ref "IMU") (pin "8") (pinfunction "CS_M_8") (pintype "bidirectional"))
      (node (ref "R6") (pin "2") (pinfunction "2_2") (pintype "passive"))
    )
    (net (code "44") (name "Net-(L2-Pad1)") (class "Default")
      (node (ref "L2") (pin "1") (pinfunction "1_1") (pintype "passive"))
      (node (ref "R13") (pin "1") (pinfunction "1_1") (pintype "passive"))
      (node (ref "R21") (pin "2") (pinfunction "2_2") (pintype "passive"))
      (node (ref "U$3") (pin "SIG") (pinfunction "SIG_SIG") (pintype "bidirectional"))
    )
    (net (code "45") (name "Net-(LED1-PadA)") (class "Default")
      (node (ref "LED1") (pin "A") (pinfunction "A_A") (pintype "passive"))
      (node (ref "R4") (pin "1") (pinfunction "1_1") (pintype "passive"))
    )
    (net (code "46") (name "Net-(LED2-PadA)") (class "Default")
      (node (ref "LED2") (pin "A") (pinfunction "A_A") (pintype "passive"))
      (node (ref "R5") (pin "1") (pinfunction "1_1") (pintype "passive"))
    )
    (net (code "47") (name "Net-(LED3-PadC)") (class "Default")
      (node (ref "LED3") (pin "C") (pinfunction "C_C") (pintype "passive"))
      (node (ref "R10") (pin "2") (pinfunction "2_2") (pintype "passive"))
    )
    (net (code "48") (name "Net-(R15-Pad1)") (class "Default")
      (node (ref "R15") (pin "1") (pinfunction "1_1") (pintype "passive"))
      (node (ref "R16") (pin "2") (pinfunction "2_2") (pintype "passive"))
      (node (ref "U$5") (pin "SIG") (pinfunction "SIG_SIG") (pintype "bidirectional"))
    )
    (net (code "49") (name "Net-(R15-Pad2)") (class "Default")
      (node (ref "R15") (pin "2") (pinfunction "2_2") (pintype "passive"))
      (node (ref "R17") (pin "1") (pinfunction "1_1") (pintype "passive"))
      (node (ref "R22") (pin "1") (pinfunction "1_1") (pintype "passive"))
      (node (ref "U$7") (pin "SIG") (pinfunction "SIG_SIG") (pintype "bidirectional"))
    )
    (net (code "50") (name "Net-(R19-Pad1)") (class "Default")
      (node (ref "R19") (pin "1") (pinfunction "1_1") (pintype "passive"))
      (node (ref "U$2") (pin "ENA") (pinfunction "ENA_ENA") (pintype "bidirectional"))
    )
    (net (code "51") (name "Net-(R20-Pad1)") (class "Default")
      (node (ref "R20") (pin "1") (pinfunction "1_1") (pintype "passive"))
      (node (ref "U$2") (pin "OUT1") (pinfunction "OUT1_OUT1") (pintype "bidirectional"))
    )
    (net (code "52") (name "Net-(U$6-ANT)") (class "Default")
      (node (ref "R13") (pin "2") (pinfunction "2_2") (pintype "passive"))
      (node (ref "R14") (pin "2") (pinfunction "2_2") (pintype "passive"))
      (node (ref "U$6") (pin "1") (pinfunction "P$1_1") (pintype "bidirectional"))
      (node (ref "U$6") (pin "10") (pinfunction "P$10_10") (pintype "bidirectional"))
      (node (ref "U$6") (pin "11") (pinfunction "P$11_11") (pintype "bidirectional"))
      (node (ref "U$6") (pin "12") (pinfunction "P$12_12") (pintype "bidirectional"))
      (node (ref "U$6") (pin "13") (pinfunction "P$13_13") (pintype "bidirectional"))
      (node (ref "U$6") (pin "14") (pinfunction "P$14_14") (pintype "bidirectional"))
      (node (ref "U$6") (pin "15") (pinfunction "P$15_15") (pintype "bidirectional"))
      (node (ref "U$6") (pin "16") (pinfunction "P$16_16") (pintype "bidirectional"))
      (node (ref "U$6") (pin "17") (pinfunction "P$17_17") (pintype "bidirectional"))
      (node (ref "U$6") (pin "18") (pinfunction "P$18_18") (pintype "bidirectional"))
      (node (ref "U$6") (pin "19") (pinfunction "P$19_19") (pintype "bidirectional"))
      (node (ref "U$6") (pin "2") (pinfunction "P$2_2") (pintype "bidirectional"))
      (node (ref "U$6") (pin "3") (pinfunction "P$3_3") (pintype "bidirectional"))
      (node (ref "U$6") (pin "4") (pinfunction "P$4_4") (pintype "bidirectional"))
      (node (ref "U$6") (pin "5") (pinfunction "P$5_5") (pintype "bidirectional"))
      (node (ref "U$6") (pin "6") (pinfunction "P$6_6") (pintype "bidirectional"))
      (node (ref "U$6") (pin "7") (pinfunction "P$7_7") (pintype "bidirectional"))
      (node (ref "U$6") (pin "8") (pinfunction "P$8_8") (pintype "bidirectional"))
      (node (ref "U$6") (pin "9") (pinfunction "P$9_9") (pintype "bidirectional"))
      (node (ref "U$6") (pin "ANTENNA") (pinfunction "ANT_ANTENNA") (pintype "bidirectional"))
    )
    (net (code "53") (name "Net-(U$8-LX)") (class "Default")
      (node (ref "L4") (pin "1") (pinfunction "1_1") (pintype "passive"))
      (node (ref "U$8") (pin "7") (pinfunction "LX_7") (pintype "bidirectional"))
    )
    (net (code "54") (name "Net-(U$8-SHDN)") (class "Default")
      (node (ref "R18") (pin "1") (pinfunction "1_1") (pintype "passive"))
      (node (ref "U$8") (pin "5") (pinfunction "SHDN_5") (pintype "bidirectional"))
    )
    (net (code "55") (name "unconnected-(GPS-GPIO1{slash}RXD1-Pad3)") (class "Default")
      (node (ref "GPS") (pin "3") (pinfunction "GPIO1/RXD1_3") (pintype "bidirectional"))
    )
    (net (code "56") (name "unconnected-(GPS-GPIO2{slash}TXD1-Pad8)") (class "Default")
      (node (ref "GPS") (pin "8") (pinfunction "GPIO2/TXD1_8") (pintype "bidirectional"))
    )
    (net (code "57") (name "unconnected-(GPS-GPIO3{slash}P1PPS1-Pad40)") (class "Default")
      (node (ref "GPS") (pin "40") (pinfunction "GPIO3/P1PPS1_40") (pintype "bidirectional"))
    )
    (net (code "58") (name "unconnected-(GPS-GPIO4{slash}SCL-Pad37)") (class "Default")
      (node (ref "GPS") (pin "37") (pinfunction "GPIO4/SCL_37") (pintype "bidirectional"))
    )
    (net (code "59") (name "unconnected-(GPS-GPIO5{slash}SDA-Pad14)") (class "Default")
      (node (ref "GPS") (pin "14") (pinfunction "GPIO5/SDA_14") (pintype "bidirectional"))
    )
    (net (code "60") (name "unconnected-(GPS-GPIO6{slash}M_CSN2-Pad13)") (class "Default")
      (node (ref "GPS") (pin "13") (pinfunction "GPIO6/M_CSN2_13") (pintype "bidirectional"))
    )
    (net (code "61") (name "unconnected-(GPS-GPIO7{slash}P1PPS2-Pad12)") (class "Default")
      (node (ref "GPS") (pin "12") (pinfunction "GPIO7/P1PPS2_12") (pintype "bidirectional"))
    )
    (net (code "62") (name "unconnected-(GPS-GPIO8-Pad51)") (class "Default")
      (node (ref "GPS") (pin "51") (pinfunction "GPIO8_51") (pintype "bidirectional"))
    )
    (net (code "63") (name "unconnected-(GPS-GPIO9-Pad47)") (class "Default")
      (node (ref "GPS") (pin "47") (pinfunction "GPIO9_47") (pintype "bidirectional"))
    )
    (net (code "64") (name "unconnected-(GPS-GPIO10-Pad59)") (class "Default")
      (node (ref "GPS") (pin "59") (pinfunction "GPIO10_59") (pintype "bidirectional"))
    )
    (net (code "65") (name "unconnected-(GPS-GPIO11-Pad63)") (class "Default")
      (node (ref "GPS") (pin "63") (pinfunction "GPIO11_63") (pintype "bidirectional"))
    )
    (net (code "66") (name "unconnected-(GPS-GPIO12-Pad55)") (class "Default")
      (node (ref "GPS") (pin "55") (pinfunction "GPIO12_55") (pintype "bidirectional"))
    )
    (net (code "67") (name "unconnected-(GPS-GPIO13-Pad50)") (class "Default")
      (node (ref "GPS") (pin "50") (pinfunction "GPIO13_50") (pintype "bidirectional"))
    )
    (net (code "68") (name "unconnected-(GPS-GPIO14-Pad45)") (class "Default")
      (node (ref "GPS") (pin "45") (pinfunction "GPIO14_45") (pintype "bidirectional"))
    )
    (net (code "69") (name "unconnected-(GPS-GPIO15-Pad53)") (class "Default")
      (node (ref "GPS") (pin "53") (pinfunction "GPIO15_53") (pintype "bidirectional"))
    )
    (net (code "70") (name "unconnected-(GPS-GPIO16-Pad48)") (class "Default")
      (node (ref "GPS") (pin "48") (pinfunction "GPIO16_48") (pintype "bidirectional"))
    )
    (net (code "71") (name "unconnected-(GPS-GPIO20-Pad54)") (class "Default")
      (node (ref "GPS") (pin "54") (pinfunction "GPIO20_54") (pintype "bidirectional"))
    )
    (net (code "72") (name "unconnected-(GPS-GPIO21-Pad57)") (class "Default")
      (node (ref "GPS") (pin "57") (pinfunction "GPIO21_57") (pintype "bidirectional"))
    )
    (net (code "73") (name "unconnected-(GPS-GPIO22-Pad46)") (class "Default")
      (node (ref "GPS") (pin "46") (pinfunction "GPIO22_46") (pintype "bidirectional"))
    )
    (net (code "74") (name "unconnected-(GPS-GPIO23{slash}M_CSN0-Pad16)") (class "Default")
      (node (ref "GPS") (pin "16") (pinfunction "GPIO23/M_CSN0_16") (pintype "bidirectional"))
    )
    (net (code "75") (name "unconnected-(GPS-GPIO24{slash}M_SCK-Pad5)") (class "Default")
      (node (ref "GPS") (pin "5") (pinfunction "GPIO24/M_SCK_5") (pintype "bidirectional"))
    )
    (net (code "76") (name "unconnected-(GPS-GPIO25{slash}M_MISO-Pad4)") (class "Default")
      (node (ref "GPS") (pin "4") (pinfunction "GPIO25/M_MISO_4") (pintype "bidirectional"))
    )
    (net (code "77") (name "unconnected-(GPS-GPIO26{slash}M_MOSI-Pad6)") (class "Default")
      (node (ref "GPS") (pin "6") (pinfunction "GPIO26/M_MOSI_6") (pintype "bidirectional"))
    )
    (net (code "78") (name "unconnected-(GPS-GPIO27-Pad52)") (class "Default")
      (node (ref "GPS") (pin "52") (pinfunction "GPIO27_52") (pintype "bidirectional"))
    )
    (net (code "79") (name "unconnected-(GPS-GPIO28{slash}MS_CSN-Pad43)") (class "Default")
      (node (ref "GPS") (pin "43") (pinfunction "GPIO28/MS_CSN_43") (pintype "bidirectional"))
    )
    (net (code "80") (name "unconnected-(GPS-GPIO29{slash}MS_SCK-Pad41)") (class "Default")
      (node (ref "GPS") (pin "41") (pinfunction "GPIO29/MS_SCK_41") (pintype "bidirectional"))
    )
    (net (code "81") (name "unconnected-(GPS-GPIO30{slash}MS_MOSI-Pad38)") (class "Default")
      (node (ref "GPS") (pin "38") (pinfunction "GPIO30/MS_MOSI_38") (pintype "bidirectional"))
    )
    (net (code "82") (name "unconnected-(GPS-GPIO31{slash}MS_MISO-Pad39)") (class "Default")
      (node (ref "GPS") (pin "39") (pinfunction "GPIO31/MS_MISO_39") (pintype "bidirectional"))
    )
    (net (code "83") (name "unconnected-(GPS-NC-Pad17)") (class "Default")
      (node (ref "GPS") (pin "17") (pinfunction "NC_17") (pintype "bidirectional"))
    )
    (net (code "84") (name "unconnected-(GPS-NC-Pad20)") (class "Default")
      (node (ref "GPS") (pin "20") (pinfunction "NC_20") (pintype "bidirectional"))
    )
    (net (code "85") (name "unconnected-(GPS-NC-Pad23)") (class "Default")
      (node (ref "GPS") (pin "23") (pinfunction "NC_23") (pintype "bidirectional"))
    )
    (net (code "86") (name "unconnected-(GPS-NC-Pad26)") (class "Default")
      (node (ref "GPS") (pin "26") (pinfunction "NC_26") (pintype "bidirectional"))
    )
    (net (code "87") (name "unconnected-(GPS-NC-Pad30)") (class "Default")
      (node (ref "GPS") (pin "30") (pinfunction "NC_30") (pintype "bidirectional"))
    )
    (net (code "88") (name "unconnected-(GPS-NC-Pad34)") (class "Default")
      (node (ref "GPS") (pin "34") (pinfunction "NC_34") (pintype "bidirectional"))
    )
    (net (code "89") (name "unconnected-(GPS-NC-Pad35)") (class "Default")
      (node (ref "GPS") (pin "35") (pinfunction "NC_35") (pintype "bidirectional"))
    )
    (net (code "90") (name "unconnected-(GPS-NC-Pad36)") (class "Default")
      (node (ref "GPS") (pin "36") (pinfunction "NC_36") (pintype "bidirectional"))
    )
    (net (code "91") (name "unconnected-(GPS-NC-Pad56)") (class "Default")
      (node (ref "GPS") (pin "56") (pinfunction "NC_56") (pintype "bidirectional"))
    )
    (net (code "92") (name "unconnected-(GPS-NC-Pad66)") (class "Default")
      (node (ref "GPS") (pin "66") (pinfunction "NC_66") (pintype "bidirectional"))
    )
    (net (code "93") (name "unconnected-(GPS-NC-Pad67)") (class "Default")
      (node (ref "GPS") (pin "67") (pinfunction "NC_67") (pintype "bidirectional"))
    )
    (net (code "94") (name "unconnected-(GPS-NC-Pad68)") (class "Default")
      (node (ref "GPS") (pin "68") (pinfunction "NC_68") (pintype "bidirectional"))
    )
    (net (code "95") (name "unconnected-(IMU-DEN_A{slash}G-Pad13)") (class "Default")
      (node (ref "IMU") (pin "13") (pinfunction "DEN_A/G_13") (pintype "bidirectional"))
    )
    (net (code "96") (name "unconnected-(IMU-INT_M-Pad10)") (class "Default")
      (node (ref "IMU") (pin "10") (pinfunction "INT_M_10") (pintype "bidirectional"))
    )
    (net (code "97") (name "unconnected-(MICROCONTROLLER-Pad14)") (class "Default")
      (node (ref "MICROCONTROLLER") (pin "14") (pinfunction "14_14") (pintype "bidirectional"))
    )
    (net (code "98") (name "unconnected-(MICROCONTROLLER-Pad15)") (class "Default")
      (node (ref "MICROCONTROLLER") (pin "15") (pinfunction "15_15") (pintype "bidirectional"))
    )
    (net (code "99") (name "unconnected-(MICROCONTROLLER-Pad16)") (class "Default")
      (node (ref "MICROCONTROLLER") (pin "16") (pinfunction "16_16") (pintype "bidirectional"))
    )
    (net (code "100") (name "unconnected-(MICROCONTROLLER-Pad17)") (class "Default")
      (node (ref "MICROCONTROLLER") (pin "17") (pinfunction "17_17") (pintype "bidirectional"))
    )
    (net (code "101") (name "unconnected-(MICROCONTROLLER-Pad21)") (class "Default")
      (node (ref "MICROCONTROLLER") (pin "21") (pinfunction "21_21") (pintype "bidirectional"))
    )
    (net (code "102") (name "unconnected-(MICROCONTROLLER-Pad29)") (class "Default")
      (node (ref "MICROCONTROLLER") (pin "29") (pinfunction "29_29") (pintype "bidirectional"))
    )
    (net (code "103") (name "unconnected-(MICROCONTROLLER-Pad30)") (class "Default")
      (node (ref "MICROCONTROLLER") (pin "30") (pinfunction "30_30") (pintype "bidirectional"))
    )
    (net (code "104") (name "unconnected-(MICROCONTROLLER-Pad31)") (class "Default")
      (node (ref "MICROCONTROLLER") (pin "31") (pinfunction "31_31") (pintype "bidirectional"))
    )
    (net (code "105") (name "unconnected-(MICROCONTROLLER-Pad38)") (class "Default")
      (node (ref "MICROCONTROLLER") (pin "38") (pinfunction "38_38") (pintype "bidirectional"))
    )
    (net (code "106") (name "unconnected-(MICROCONTROLLER-Pad39)") (class "Default")
      (node (ref "MICROCONTROLLER") (pin "39") (pinfunction "39_39") (pintype "input"))
    )
    (net (code "107") (name "unconnected-(MICROCONTROLLER-Pad42)") (class "Default")
      (node (ref "MICROCONTROLLER") (pin "42") (pinfunction "42_42") (pintype "bidirectional"))
    )
    (net (code "108") (name "unconnected-(MICROCONTROLLER-Pad43)") (class "Default")
      (node (ref "MICROCONTROLLER") (pin "43") (pinfunction "43_43") (pintype "bidirectional"))
    )
    (net (code "109") (name "unconnected-(U$5-PadNC)") (class "Default")
      (node (ref "U$5") (pin "NC") (pinfunction "NC_NC") (pintype "bidirectional"))
    )
    (net (code "110") (name "unconnected-(U$8-LBI-Pad2)") (class "Default")
      (node (ref "U$8") (pin "2") (pinfunction "LBI_2") (pintype "bidirectional"))
    )
    (net (code "111") (name "unconnected-(U$8-LBO-Pad3)") (class "Default")
      (node (ref "U$8") (pin "3") (pinfunction "LBO_3") (pintype "bidirectional"))
    )
    (net (code "112") (name "unconnected-(U$8-REF-Pad4)") (class "Default")
      (node (ref "U$8") (pin "4") (pinfunction "REF_4") (pintype "bidirectional"))
    )
  )
)
